# JacdacTopologyHubEc30_126.net
KiCad netlist of a schematic drawn in Altium Designer
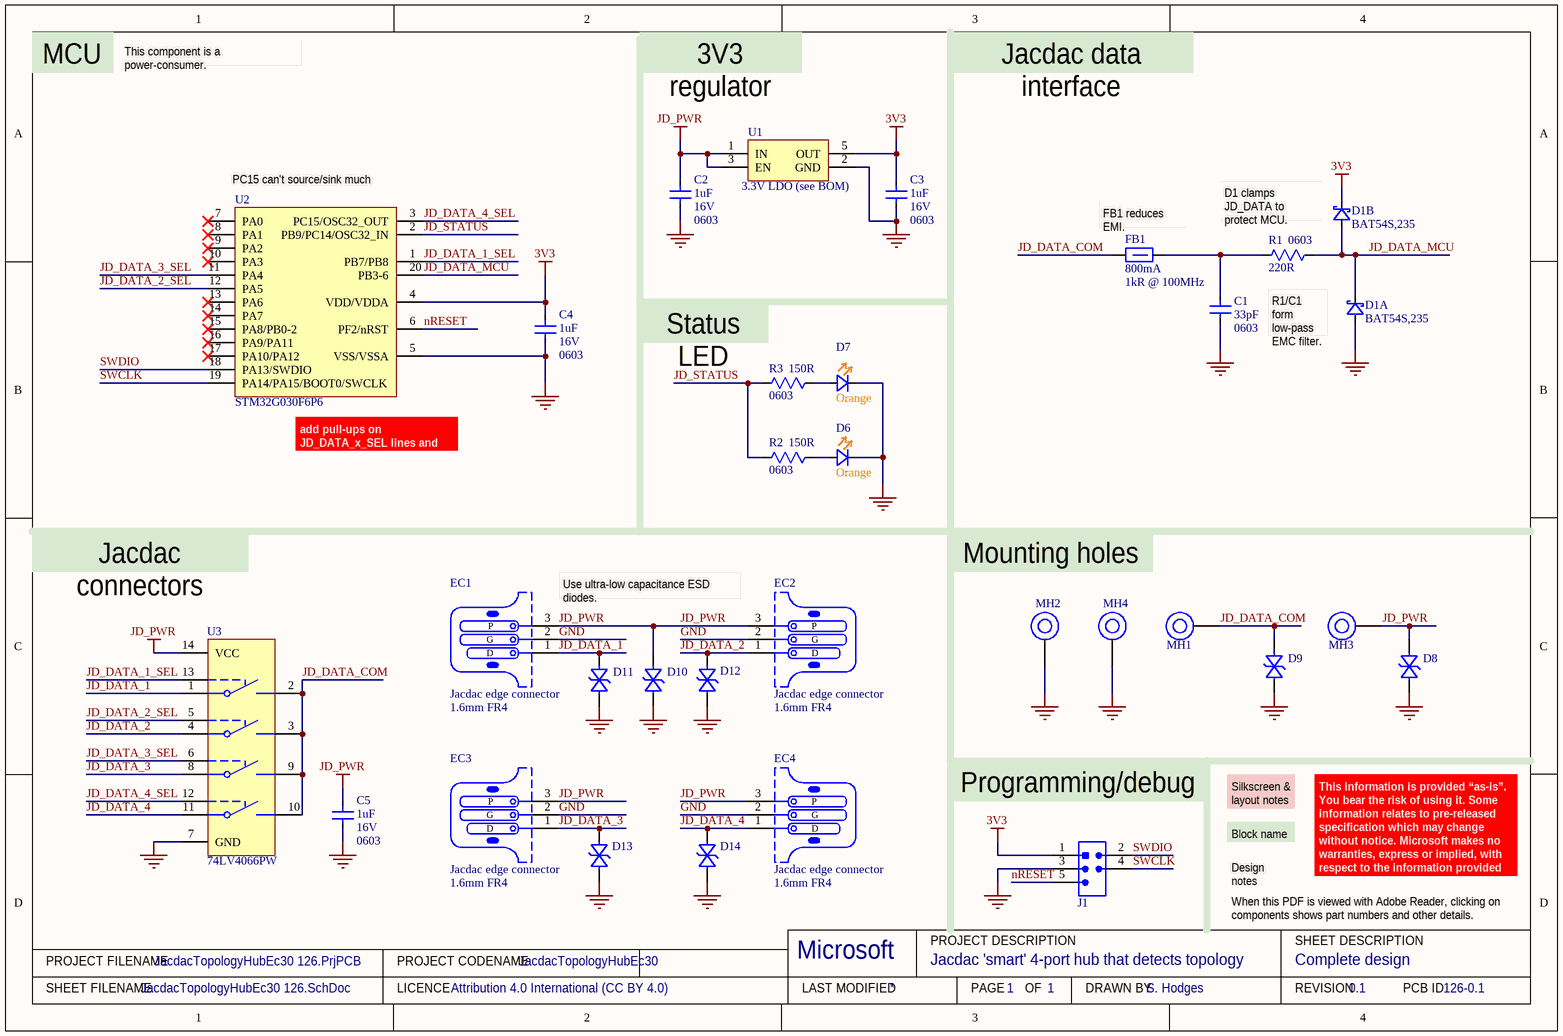
[diagram p0: JacdacTopologyHubEc30 126.SchDoc]

(export (version "E")
  (design (tool "Eeschema 10.0.6"))
  (components
    (comp (ref "C1")
      (value "33pF")
      (footprint "YAGEO-0603:CC0603")
      (description "Cap 33PF 50V 0603 SMD 5% NP0")
      (fields
        (field (name "MANUFACTURER") "Yageo")
        (field (name "MANUFACTURER PART NUMBER") "CC0603JRNPO9BN330")
        (field (name "CAPACITANCE") "33pF")
        (field (name "CASE/PACKAGE") "0603")
      )
      (libsource (lib "Yageo") (part "CC0603JRNPO9BN330"))
    )
    (comp (ref "C2")
      (value "1uF 16V")
      (footprint "SAMSUNG-CAP-0603:C0603 - without outline")
      (description "SMD Multilayer Ceramic Capacitor, 1 µF, 16 V, 0603 [1608 Metric], ± 10%, X5R, CL Series")
      (fields
        (field (name "MANUFACTURER") "Samsung")
        (field (name "MANUFACTURER PART NUMBER") "CL10A105KO8NNNC")
        (field (name "VOLTAGE") "16V")
        (field (name "CASE/PACKAGE") "0603")
        (field (name "CAPACITANCE") "1uF")
      )
      (libsource (lib "Samsung") (part "CL10A105KO8NNNC"))
    )
    (comp (ref "C3")
      (value "1uF 16V")
      (footprint "SAMSUNG-CAP-0603:C0603 - without outline")
      (description "SMD Multilayer Ceramic Capacitor, 1 µF, 16 V, 0603 [1608 Metric], ± 10%, X5R, CL Series")
      (fields
        (field (name "MANUFACTURER") "Samsung")
        (field (name "MANUFACTURER PART NUMBER") "CL10A105KO8NNNC")
        (field (name "VOLTAGE") "16V")
        (field (name "CASE/PACKAGE") "0603")
        (field (name "CAPACITANCE") "1uF")
      )
      (libsource (lib "Samsung") (part "CL10A105KO8NNNC"))
    )
    (comp (ref "C4")
      (value "1uF 16V")
      (footprint "SAMSUNG-CAP-0603:C0603 - without outline")
      (description "SMD Multilayer Ceramic Capacitor, 1 µF, 16 V, 0603 [1608 Metric], ± 10%, X5R, CL Series")
      (fields
        (field (name "MANUFACTURER") "Samsung")
        (field (name "MANUFACTURER PART NUMBER") "CL10A105KO8NNNC")
        (field (name "VOLTAGE") "16V")
        (field (name "CASE/PACKAGE") "0603")
        (field (name "CAPACITANCE") "1uF")
      )
      (libsource (lib "Samsung") (part "CL10A105KO8NNNC"))
    )
    (comp (ref "C5")
      (value "1uF 16V")
      (footprint "SAMSUNG-CAP-0603:C0603 - without outline")
      (description "SMD Multilayer Ceramic Capacitor, 1 µF, 16 V, 0603 [1608 Metric], ± 10%, X5R, CL Series")
      (fields
        (field (name "MANUFACTURER") "Samsung")
        (field (name "MANUFACTURER PART NUMBER") "CL10A105KO8NNNC")
        (field (name "VOLTAGE") "16V")
        (field (name "CASE/PACKAGE") "0603")
        (field (name "CAPACITANCE") "1uF")
      )
      (libsource (lib "Samsung") (part "CL10A105KO8NNNC"))
    )
    (comp (ref "D1")
      (value "BAT54S")
      (footprint "NXP-BAT54S:NXP-BAT54S-TO-236AB - without outline")
      (description "DIODE ARRAY SCHOTTKY 30V SOT23")
      (fields (field (name "MANUFACTURER") "Nexperia") (field (name "MANUFACTURER PART NUMBER") "BAT54S,235"))
      (libsource (lib "NXP") (part "BAT54S"))
    )
    (comp (ref "D6")
      (value "~")
      (footprint "0603 Orange")
      (description "LED ORANGE DIFFUSED 0603 SMD")
      (fields
        (field (name "MANUFACTURER") "Everlight Elec")
        (field (name "MANUFACTURER PART NUMBER") "19-217/S2C-AQ1R1B/3T")
        (field (name "COLOUR") "Orange")
      )
      (libsource (lib "EverlightElec") (part "19-217/S2C-AQ1R1B/3T"))
    )
    (comp (ref "D7")
      (value "~")
      (footprint "0603 Orange")
      (description "LED ORANGE DIFFUSED 0603 SMD")
      (fields
        (field (name "MANUFACTURER") "Everlight Elec")
        (field (name "MANUFACTURER PART NUMBER") "19-217/S2C-AQ1R1B/3T")
        (field (name "COLOUR") "Orange")
      )
      (libsource (lib "EverlightElec") (part "19-217/S2C-AQ1R1B/3T"))
    )
    (comp (ref "D8")
      (value "RCLAMP0521P-N")
      (footprint "0402:TVS 0402 - XL")
      (description "Bidirectional 5V (Max) 6V 16V 3.5A (8/20us) 0402 TVS RoHS")
      (fields
        (field (name "MANUFACTURER") "Born Semiconductor")
        (field (name "CREATED BY") "D Gakure")
        (field (name "CHECKED BY") "?")
      )
      (libsource (lib "BornSemiconductor") (part "RCLAMP0521P-N"))
    )
    (comp (ref "D9")
      (value "RCLAMP0521P-N")
      (footprint "0402:TVS 0402 - XL")
      (description "Bidirectional 5V (Max) 6V 16V 3.5A (8/20us) 0402 TVS RoHS")
      (fields
        (field (name "MANUFACTURER") "Born Semiconductor")
        (field (name "CREATED BY") "D Gakure")
        (field (name "CHECKED BY") "?")
      )
      (libsource (lib "BornSemiconductor") (part "RCLAMP0521P-N"))
    )
    (comp (ref "D10")
      (value "RCLAMP0521P-N")
      (footprint "0402:TVS 0402 - XL")
      (description "Bidirectional 5V (Max) 6V 16V 3.5A (8/20us) 0402 TVS RoHS")
      (fields
        (field (name "MANUFACTURER") "Born Semiconductor")
        (field (name "CREATED BY") "D Gakure")
        (field (name "CHECKED BY") "?")
      )
      (libsource (lib "BornSemiconductor") (part "RCLAMP0521P-N"))
    )
    (comp (ref "D11")
      (value "RCLAMP0521P-N")
      (footprint "0402:TVS 0402 - XL")
      (description "Bidirectional 5V (Max) 6V 16V 3.5A (8/20us) 0402 TVS RoHS")
      (fields
        (field (name "MANUFACTURER") "Born Semiconductor")
        (field (name "CREATED BY") "D Gakure")
        (field (name "CHECKED BY") "?")
      )
      (libsource (lib "BornSemiconductor") (part "RCLAMP0521P-N"))
    )
    (comp (ref "D12")
      (value "RCLAMP0521P-N")
      (footprint "0402:TVS 0402 - XL")
      (description "Bidirectional 5V (Max) 6V 16V 3.5A (8/20us) 0402 TVS RoHS")
      (fields
        (field (name "MANUFACTURER") "Born Semiconductor")
        (field (name "MANUFACTURER PART NUMBER") "RCLAMP0521 (see BOM)")
        (field (name "CREATED BY") "D Gakure")
        (field (name "CHECKED BY") "?")
      )
      (libsource (lib "BornSemiconductor") (part "RCLAMP0521P-N"))
    )
    (comp (ref "D13")
      (value "RCLAMP0521P-N")
      (footprint "0402:TVS 0402 - XL")
      (description "Bidirectional 5V (Max) 6V 16V 3.5A (8/20us) 0402 TVS RoHS")
      (fields
        (field (name "MANUFACTURER") "Born Semiconductor")
        (field (name "MANUFACTURER PART NUMBER") "RCLAMP0521 (see BOM)")
        (field (name "CREATED BY") "D Gakure")
        (field (name "CHECKED BY") "?")
      )
      (libsource (lib "BornSemiconductor") (part "RCLAMP0521P-N"))
    )
    (comp (ref "D14")
      (value "RCLAMP0521P-N")
      (footprint "0402:TVS 0402 - XL")
      (description "Bidirectional 5V (Max) 6V 16V 3.5A (8/20us) 0402 TVS RoHS")
      (fields
        (field (name "MANUFACTURER") "Born Semiconductor")
        (field (name "MANUFACTURER PART NUMBER") "RCLAMP0521 (see BOM)")
        (field (name "CREATED BY") "D Gakure")
        (field (name "CHECKED BY") "?")
      )
      (libsource (lib "BornSemiconductor") (part "RCLAMP0521P-N"))
    )
    (comp (ref "EC1")
      (value "Jacdac edge connector")
      (footprint "Jacdac_edge_connector:JACDAC_EDGE_CONNECTOR_TRACES_0.15MM")
      (description "3 pin Jacdac edge connector 1.27mm pitch")
      (fields
        (field (name "MANUFACTURER PART NUMBER") "n/a")
        (field (name "PCB TYPE") "1.6mm FR4")
        (field (name "CREATED BY") "D. Gakure & S. Hodges")
      )
      (libsource (lib "") (part "Jacdac edge connector_1"))
    )
    (comp (ref "EC2")
      (value "Jacdac edge connector")
      (footprint "Jacdac_edge_connector:JACDAC_EDGE_CONNECTOR_TRACES_0.15MM")
      (description "3 pin Jacdac edge connector 1.27mm pitch")
      (fields
        (field (name "MANUFACTURER PART NUMBER") "n/a")
        (field (name "PCB TYPE") "1.6mm FR4")
        (field (name "CREATED BY") "D. Gakure & S. Hodges")
      )
      (libsource (lib "generic-con") (part "Jacdac edge connector"))
    )
    (comp (ref "EC3")
      (value "Jacdac edge connector")
      (footprint "Jacdac_edge_connector:JACDAC_EDGE_CONNECTOR_TRACES_0.15MM")
      (description "3 pin Jacdac edge connector 1.27mm pitch")
      (fields
        (field (name "MANUFACTURER PART NUMBER") "n/a")
        (field (name "PCB TYPE") "1.6mm FR4")
        (field (name "CREATED BY") "D. Gakure & S. Hodges")
      )
      (libsource (lib "") (part "Jacdac edge connector_1"))
    )
    (comp (ref "EC4")
      (value "Jacdac edge connector")
      (footprint "Jacdac_edge_connector:JACDAC_EDGE_CONNECTOR_TRACES_0.15MM")
      (description "3 pin Jacdac edge connector 1.27mm pitch")
      (fields
        (field (name "MANUFACTURER PART NUMBER") "n/a")
        (field (name "PCB TYPE") "1.6mm FR4")
        (field (name "CREATED BY") "D. Gakure & S. Hodges")
      )
      (libsource (lib "generic-con") (part "Jacdac edge connector"))
    )
    (comp (ref "FB1")
      (value "TDK MPZ1608S102ATA00")
      (footprint "TDK MPZ1608 0.8mm - without outline")
      (description "0603 1k@100MHz 0.8A chip")
      (fields
        (field (name "TOLERANCE") "25%")
        (field (name "MANUFACTURER") "TDK")
        (field (name "CURRENT RATING") "800mA")
        (field (name "IMPEDANCE") "1kR @ 100MHz")
      )
      (libsource (lib "TDK") (part "TDK MPZ1608S102ATA00"))
    )
    (comp (ref "J1")
      (value "Hack Connect Mini 1.27 mm pitch 2-row")
      (footprint "HackConnect:HACK_CONNECT_MINI_5_X_1_27")
      (libsource (lib "generic-con") (part "HACK_CONNECT_MINI"))
    )
    (comp (ref "MH1")
      (value "MH_6.5MMK_4.5MMC_3.0MMD_PTH")
      (footprint "MH_6.5MMK_4.5MMC_3.0MMD_PTH")
      (description "Mounting Hole 6.5mm keepout, 4.5mm annualar ring and 3.0mm Drill PTH")
      (libsource (lib "generic") (part "MH_6.5MMK_4.5MMC_3.0MMD_PTH"))
    )
    (comp (ref "MH2")
      (value "MH_6.5MMK_4.5MMC_3.0MMD_PTH")
      (footprint "MH_6.5MMK_4.5MMC_3.0MMD_PTH")
      (description "Mounting Hole 6.5mm keepout, 4.5mm annualar ring and 3.0mm Drill PTH")
      (libsource (lib "generic") (part "MH_6.5MMK_4.5MMC_3.0MMD_PTH"))
    )
    (comp (ref "MH3")
      (value "MH_6.5MMK_4.5MMC_3.0MMD_PTH")
      (footprint "MH_6.5MMK_4.5MMC_3.0MMD_PTH")
      (description "Mounting Hole 6.5mm keepout, 4.5mm annualar ring and 3.0mm Drill PTH")
      (libsource (lib "generic") (part "MH_6.5MMK_4.5MMC_3.0MMD_PTH"))
    )
    (comp (ref "MH4")
      (value "MH_6.5MMK_4.5MMC_3.0MMD_PTH")
      (footprint "MH_6.5MMK_4.5MMC_3.0MMD_PTH")
      (description "Mounting Hole 6.5mm keepout, 4.5mm annualar ring and 3.0mm Drill PTH")
      (libsource (lib "generic") (part "MH_6.5MMK_4.5MMC_3.0MMD_PTH"))
    )
    (comp (ref "R1")
      (value "220R")
      (footprint "YAGEO-0603:RC0603")
      (description "Res Thick Film 0603 220 Ohm 1% 0.1W(1/10W) ±100ppm/°C Pad SMD T/R")
      (fields
        (field (name "TOLERANCE") "1%")
        (field (name "RESISTANCE") "220R")
        (field (name "CASE/PACKAGE") "0603")
      )
      (libsource (lib "Yageo") (part "RC0603FR-07220RL"))
    )
    (comp (ref "R2")
      (value "150R")
      (footprint "YAGEO-0603:RC0603")
      (description "Res General Purpose Thick Film 0603 150 Ohm 1% 1/10W ±100ppm/°C Molded SMD Paper T/R")
      (fields
        (field (name "MANUFACTURER") "Yageo")
        (field (name "MANUFACTURER PART NUMBER") "RC0603FR-07150RL")
        (field (name "CASE/PACKAGE") "0603")
        (field (name "RESISTANCE") "150R")
      )
      (libsource (lib "Yageo") (part "RC0603FR-07150RL"))
    )
    (comp (ref "R3")
      (value "150R")
      (footprint "YAGEO-0603:RC0603")
      (description "Res General Purpose Thick Film 0603 150 Ohm 1% 1/10W ±100ppm/°C Molded SMD Paper T/R")
      (fields
        (field (name "MANUFACTURER") "Yageo")
        (field (name "MANUFACTURER PART NUMBER") "RC0603FR-07150RL")
        (field (name "CASE/PACKAGE") "0603")
        (field (name "RESISTANCE") "150R")
      )
      (libsource (lib "Yageo") (part "RC0603FR-07150RL"))
    )
    (comp (ref "U1")
      (value "3.3V LDO (see BOM)")
      (footprint "MICRONE-SOT23-5")
      (description "6V 260mV @ 200mA(typ) - - Fixed 3.3V SOT-23-5 Linear Voltage Regulators (LDO) ROHS")
      (fields
        (field (name "MANUFACTURER") "MICRONE(Nanjing Micro One Elec)")
        (field (name "MANUFACTURER PART NUMBER") "ME6211C33M5G-N")
        (field (name "CREATED") "DG")
        (field (name "CHECKED") "?")
      )
      (libsource (lib "MICRONE(NanjingMicroOneElec)") (part "ME6211C33M5G-N"))
    )
    (comp (ref "U2")
      (value "STM32G030F6P6")
      (footprint "ST-STM32F030F4P6:20-TSSOP - WITHOUT OUTLINE")
      (description "ARM® Cortex®-M0+ series IC 64MHz 32KB 20-TSSOP")
      (libsource (lib "ST") (part "STM32G030F6P6"))
    )
    (comp (ref "U3")
      (value "~")
      (footprint "NXP-TSSOP-14:TSSOP-14")
      (description "74LV Series 3.3 V SMT CMOS Low On Resistance Quad Bilateral Switch - TSSOP-14")
      (fields (field (name "MANUFACTURER PART NUMBER 1") "74LV4066PW"))
      (libsource (lib "NXP") (part "74LV4066PW"))
    )
  )
  (nets
    (net (code "1") (name "/JD_DATA_1") (class "Default")
      (node (ref "D11") (pin "1") (pinfunction "K_1") (pintype "passive"))
      (node (ref "EC1") (pin "1") (pinfunction "D_1") (pintype "passive"))
      (node (ref "U3") (pin "1") (pinfunction "1Y_1") (pintype "passive"))
    )
    (net (code "2") (name "/JD_DATA_1_SEL") (class "Default")
      (node (ref "U2") (pin "1") (pinfunction "PB7/PB8_1") (pintype "passive"))
      (node (ref "U3") (pin "13") (pinfunction "1E_13") (pintype "passive"))
    )
    (net (code "3") (name "/JD_DATA_2") (class "Default")
      (node (ref "D12") (pin "1") (pinfunction "K_1") (pintype "passive"))
      (node (ref "EC2") (pin "1") (pinfunction "D_1") (pintype "passive"))
      (node (ref "U3") (pin "4") (pinfunction "2Y_4") (pintype "passive"))
    )
    (net (code "4") (name "/JD_DATA_2_SEL") (class "Default")
      (node (ref "U2") (pin "12") (pinfunction "PA5_12") (pintype "passive"))
      (node (ref "U3") (pin "5") (pinfunction "2E_5") (pintype "passive"))
    )
    (net (code "5") (name "/JD_DATA_3") (class "Default")
      (node (ref "D13") (pin "1") (pinfunction "K_1") (pintype "passive"))
      (node (ref "EC3") (pin "1") (pinfunction "D_1") (pintype "passive"))
      (node (ref "U3") (pin "8") (pinfunction "3Y_8") (pintype "passive"))
    )
    (net (code "6") (name "/JD_DATA_3_SEL") (class "Default")
      (node (ref "U2") (pin "11") (pinfunction "PA4_11") (pintype "passive"))
      (node (ref "U3") (pin "6") (pinfunction "3E_6") (pintype "passive"))
    )
    (net (code "7") (name "/JD_DATA_4") (class "Default")
      (node (ref "D14") (pin "1") (pinfunction "K_1") (pintype "passive"))
      (node (ref "EC4") (pin "1") (pinfunction "D_1") (pintype "passive"))
      (node (ref "U3") (pin "11") (pinfunction "4Y_11") (pintype "passive"))
    )
    (net (code "8") (name "/JD_DATA_4_SEL") (class "Default")
      (node (ref "U2") (pin "3") (pinfunction "PC15/OSC32_OUT_3") (pintype "passive"))
      (node (ref "U3") (pin "12") (pinfunction "4E_12") (pintype "passive"))
    )
    (net (code "9") (name "/JD_DATA_COM") (class "Default")
      (node (ref "D9") (pin "1") (pinfunction "K_1") (pintype "passive"))
      (node (ref "FB1") (pin "1") (pinfunction "1_1") (pintype "passive"))
      (node (ref "MH1") (pin "1") (pinfunction "1_1") (pintype "passive"))
      (node (ref "U3") (pin "10") (pinfunction "4Z_10") (pintype "passive"))
      (node (ref "U3") (pin "2") (pinfunction "1Z_2") (pintype "passive"))
      (node (ref "U3") (pin "3") (pinfunction "2Z_3") (pintype "passive"))
      (node (ref "U3") (pin "9") (pinfunction "3Z_9") (pintype "passive"))
    )
    (net (code "10") (name "/JD_DATA_MCU") (class "Default")
      (node (ref "D1") (pin "3") (pinfunction "K_3") (pintype "passive"))
      (node (ref "R1") (pin "2") (pinfunction "2_2") (pintype "passive"))
      (node (ref "U2") (pin "20") (pinfunction "PB3-6_20") (pintype "power_in"))
    )
    (net (code "11") (name "/JD_STATUS") (class "Default")
      (node (ref "R2") (pin "1") (pinfunction "1_1") (pintype "passive"))
      (node (ref "R3") (pin "1") (pinfunction "1_1") (pintype "passive"))
      (node (ref "U2") (pin "2") (pinfunction "PB9/PC14/OSC32_IN_2") (pintype "passive"))
    )
    (net (code "12") (name "/SWCLK") (class "Default")
      (node (ref "J1") (pin "4") (pinfunction "SWCLK_4") (pintype "passive"))
      (node (ref "U2") (pin "19") (pinfunction "PA14/PA15/BOOT0/SWCLK_19") (pintype "passive"))
    )
    (net (code "13") (name "/SWDIO") (class "Default")
      (node (ref "J1") (pin "2") (pinfunction "SWDIO_2") (pintype "passive"))
      (node (ref "U2") (pin "18") (pinfunction "PA13/SWDIO_18") (pintype "passive"))
    )
    (net (code "14") (name "/nRESET") (class "Default")
      (node (ref "J1") (pin "5") (pinfunction "RESET_5") (pintype "passive"))
      (node (ref "U2") (pin "6") (pinfunction "PF2/nRST_6") (pintype "power_in"))
    )
    (net (code "15") (name "3V3") (class "Default")
      (node (ref "C3") (pin "2") (pinfunction "2_2") (pintype "passive"))
      (node (ref "C4") (pin "2") (pinfunction "2_2") (pintype "passive"))
      (node (ref "D1") (pin "2") (pinfunction "K_2") (pintype "passive"))
      (node (ref "J1") (pin "1") (pinfunction "VCC_1") (pintype "passive"))
      (node (ref "U1") (pin "5") (pinfunction "OUT_5") (pintype "passive"))
      (node (ref "U2") (pin "4") (pinfunction "VDD/VDDA_4") (pintype "passive"))
    )
    (net (code "16") (name "GND") (class "Default")
      (node (ref "C1") (pin "1") (pinfunction "1_1") (pintype "passive"))
      (node (ref "C2") (pin "1") (pinfunction "1_1") (pintype "passive"))
      (node (ref "C3") (pin "1") (pinfunction "1_1") (pintype "passive"))
      (node (ref "C4") (pin "1") (pinfunction "1_1") (pintype "passive"))
      (node (ref "C5") (pin "1") (pinfunction "1_1") (pintype "passive"))
      (node (ref "D1") (pin "1") (pinfunction "A_1") (pintype "passive"))
      (node (ref "D10") (pin "2") (pinfunction "A_2") (pintype "passive"))
      (node (ref "D11") (pin "2") (pinfunction "A_2") (pintype "passive"))
      (node (ref "D12") (pin "2") (pinfunction "A_2") (pintype "passive"))
      (node (ref "D13") (pin "2") (pinfunction "A_2") (pintype "passive"))
      (node (ref "D14") (pin "2") (pinfunction "A_2") (pintype "passive"))
      (node (ref "D6") (pin "1") (pinfunction "K_1") (pintype "passive"))
      (node (ref "D7") (pin "1") (pinfunction "K_1") (pintype "passive"))
      (node (ref "D8") (pin "2") (pinfunction "A_2") (pintype "passive"))
      (node (ref "D9") (pin "2") (pinfunction "A_2") (pintype "passive"))
      (node (ref "EC1") (pin "2") (pinfunction "G_2") (pintype "passive"))
      (node (ref "EC2") (pin "2") (pinfunction "G_2") (pintype "passive"))
      (node (ref "EC3") (pin "2") (pinfunction "G_2") (pintype "passive"))
      (node (ref "EC4") (pin "2") (pinfunction "G_2") (pintype "passive"))
      (node (ref "J1") (pin "3") (pinfunction "GND_3") (pintype "passive"))
      (node (ref "MH2") (pin "1") (pinfunction "1_1") (pintype "passive"))
      (node (ref "MH4") (pin "1") (pinfunction "1_1") (pintype "passive"))
      (node (ref "U1") (pin "2") (pinfunction "GND_2") (pintype "passive"))
      (node (ref "U2") (pin "5") (pinfunction "VSS/VSSA_5") (pintype "power_in"))
      (node (ref "U3") (pin "7") (pinfunction "GND_7") (pintype "passive"))
    )
    (net (code "17") (name "JD_PWR") (class "Default")
      (node (ref "C2") (pin "2") (pinfunction "2_2") (pintype "passive"))
      (node (ref "C5") (pin "2") (pinfunction "2_2") (pintype "passive"))
      (node (ref "D10") (pin "1") (pinfunction "K_1") (pintype "passive"))
      (node (ref "D8") (pin "1") (pinfunction "K_1") (pintype "passive"))
      (node (ref "EC1") (pin "3") (pinfunction "P_3") (pintype "passive"))
      (node (ref "EC2") (pin "3") (pinfunction "P_3") (pintype "passive"))
      (node (ref "EC3") (pin "3") (pinfunction "P_3") (pintype "passive"))
      (node (ref "EC4") (pin "3") (pinfunction "P_3") (pintype "passive"))
      (node (ref "MH3") (pin "1") (pinfunction "1_1") (pintype "passive"))
      (node (ref "U1") (pin "1") (pinfunction "IN_1") (pintype "passive"))
      (node (ref "U1") (pin "3") (pinfunction "EN_3") (pintype "passive"))
      (node (ref "U3") (pin "14") (pinfunction "VCC_14") (pintype "passive"))
    )
    (net (code "18") (name "Net-(C1-Pad2)") (class "Default")
      (node (ref "C1") (pin "2") (pinfunction "2_2") (pintype "passive"))
      (node (ref "FB1") (pin "2") (pinfunction "2_2") (pintype "passive"))
      (node (ref "R1") (pin "1") (pinfunction "1_1") (pintype "passive"))
    )
    (net (code "19") (name "Net-(D6-A)") (class "Default")
      (node (ref "D6") (pin "2") (pinfunction "A_2") (pintype "passive"))
      (node (ref "R2") (pin "2") (pinfunction "2_2") (pintype "passive"))
    )
    (net (code "20") (name "Net-(D7-A)") (class "Default")
      (node (ref "D7") (pin "2") (pinfunction "A_2") (pintype "passive"))
      (node (ref "R3") (pin "2") (pinfunction "2_2") (pintype "passive"))
    )
    (net (code "21") (name "unconnected-(U2-PA0-Pad7)") (class "Default")
      (node (ref "U2") (pin "7") (pinfunction "PA0_7") (pintype "passive+no_connect"))
    )
    (net (code "22") (name "unconnected-(U2-PA1-Pad8)") (class "Default")
      (node (ref "U2") (pin "8") (pinfunction "PA1_8") (pintype "passive+no_connect"))
    )
    (net (code "23") (name "unconnected-(U2-PA2-Pad9)") (class "Default")
      (node (ref "U2") (pin "9") (pinfunction "PA2_9") (pintype "passive+no_connect"))
    )
    (net (code "24") (name "unconnected-(U2-PA3-Pad10)") (class "Default")
      (node (ref "U2") (pin "10") (pinfunction "PA3_10") (pintype "passive+no_connect"))
    )
    (net (code "25") (name "unconnected-(U2-PA6-Pad13)") (class "Default")
      (node (ref "U2") (pin "13") (pinfunction "PA6_13") (pintype "passive+no_connect"))
    )
    (net (code "26") (name "unconnected-(U2-PA7-Pad14)") (class "Default")
      (node (ref "U2") (pin "14") (pinfunction "PA7_14") (pintype "passive+no_connect"))
    )
    (net (code "27") (name "unconnected-(U2-PA8{slash}PB0-2-Pad15)") (class "Default")
      (node (ref "U2") (pin "15") (pinfunction "PA8/PB0-2_15") (pintype "passive+no_connect"))
    )
    (net (code "28") (name "unconnected-(U2-PA9{slash}PA11-Pad16)") (class "Default")
      (node (ref "U2") (pin "16") (pinfunction "PA9/PA11_16") (pintype "passive+no_connect"))
    )
    (net (code "29") (name "unconnected-(U2-PA10{slash}PA12-Pad17)") (class "Default")
      (node (ref "U2") (pin "17") (pinfunction "PA10/PA12_17") (pintype "passive+no_connect"))
    )
  )
)
